# lcTempLogger.net
KiCad netlist of a schematic drawn in EAGLE
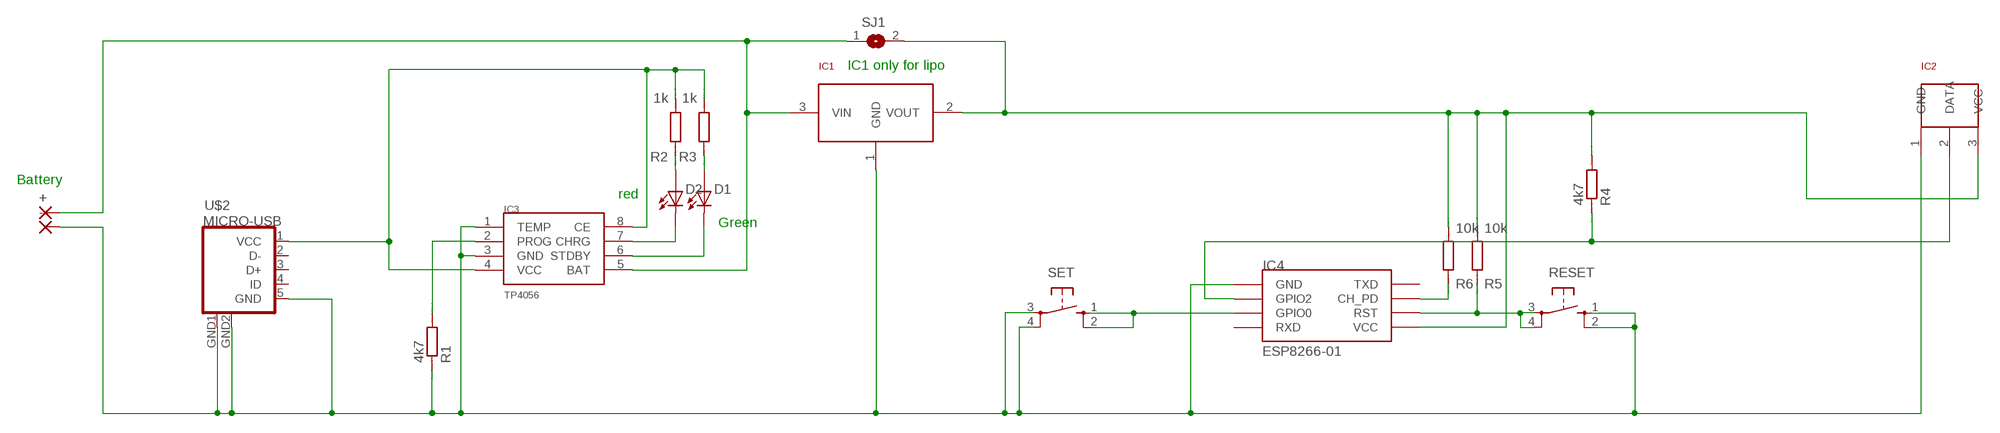
[diagram p0: schematic, sheet 1]

(export (version "E")
  (design (tool "Eeschema 10.0.6"))
  (components
    (comp (ref "+")
      (value "1,6/0,8")
      (footprint "eagle-import:1,6_0,8")
      (libsource (lib "eagle-import") (part "1,6/0,8"))
    )
    (comp (ref "-")
      (value "1,6/0,8")
      (footprint "eagle-import:1,6_0,8")
      (libsource (lib "eagle-import") (part "1,6/0,8"))
    )
    (comp (ref "D1")
      (value "LED-0805")
      (footprint "eagle-import:CHIPLED_0805")
      (libsource (lib "eagle-import") (part "LED-0805"))
    )
    (comp (ref "D2")
      (value "LED-0805")
      (footprint "eagle-import:CHIPLED_0805")
      (libsource (lib "eagle-import") (part "LED-0805"))
    )
    (comp (ref "IC1")
      (value "MCP1700")
      (footprint "eagle-import:SOT-23")
      (libsource (lib "eagle-import") (part "MCP1700SOT-32"))
    )
    (comp (ref "IC2")
      (value "DS18B20TO-92")
      (footprint "eagle-import:TO-92")
      (libsource (lib "eagle-import") (part "DS18B20TO-92"))
    )
    (comp (ref "IC3")
      (value "TP4056")
      (footprint "eagle-import:SOP-8")
      (libsource (lib "eagle-import") (part "TP4056"))
    )
    (comp (ref "IC4")
      (value "ESP8266-01")
      (footprint "eagle-import:ESP01")
      (libsource (lib "eagle-import") (part "ESP8266-01"))
    )
    (comp (ref "R1")
      (value "4k7")
      (footprint "eagle-import:R1206")
      (libsource (lib "eagle-import") (part "RR1206"))
    )
    (comp (ref "R2")
      (value "1k")
      (footprint "eagle-import:R0805")
      (libsource (lib "eagle-import") (part "R"))
    )
    (comp (ref "R3")
      (value "1k")
      (footprint "eagle-import:R0805")
      (libsource (lib "eagle-import") (part "R"))
    )
    (comp (ref "R4")
      (value "4k7")
      (footprint "eagle-import:R1206")
      (libsource (lib "eagle-import") (part "RR1206"))
    )
    (comp (ref "R5")
      (value "10k")
      (footprint "eagle-import:R1206")
      (libsource (lib "eagle-import") (part "RR1206"))
    )
    (comp (ref "R6")
      (value "10k")
      (footprint "eagle-import:R1206")
      (libsource (lib "eagle-import") (part "RR1206"))
    )
    (comp (ref "RESET")
      (value "10-XX")
      (footprint "eagle-import:B3F-10XX")
      (libsource (lib "eagle-import") (part "10-XX"))
    )
    (comp (ref "SET")
      (value "10-XX")
      (footprint "eagle-import:B3F-10XX")
      (libsource (lib "eagle-import") (part "10-XX"))
    )
    (comp (ref "SJ1") (value "SJ") (footprint "eagle-import:SJ") (libsource (lib "eagle-import") (part "SJ")))
    (comp (ref "U$2")
      (value "MICRO-USB")
      (footprint "eagle-import:MICRO-USB")
      (libsource (lib "eagle-import") (part "MICRO-USB"))
    )
  )
  (nets
    (net (code "1") (name "Net-(+-P)") (class "Default")
      (node (ref "+") (pin "1") (pinfunction "P_1") (pintype "passive"))
      (node (ref "IC1") (pin "3") (pinfunction "VIN_3") (pintype "bidirectional"))
      (node (ref "IC3") (pin "5") (pinfunction "BAT_5") (pintype "bidirectional"))
      (node (ref "SJ1") (pin "1") (pinfunction "1_1") (pintype "passive"))
    )
    (net (code "2") (name "Net-(--P)") (class "Default")
      (node (ref "-") (pin "1") (pinfunction "P_1") (pintype "passive"))
      (node (ref "IC1") (pin "1") (pinfunction "GND_1") (pintype "bidirectional"))
      (node (ref "IC2") (pin "1") (pinfunction "GND_1") (pintype "bidirectional"))
      (node (ref "IC3") (pin "1") (pinfunction "TEMP_1") (pintype "bidirectional"))
      (node (ref "IC3") (pin "3") (pinfunction "GND_3") (pintype "bidirectional"))
      (node (ref "IC4") (pin "GND") (pinfunction "GND_GND") (pintype "bidirectional"))
      (node (ref "R1") (pin "1") (pinfunction "1_1") (pintype "passive"))
      (node (ref "RESET") (pin "1") (pinfunction "1_1") (pintype "passive"))
      (node (ref "RESET") (pin "2") (pinfunction "2_2") (pintype "passive"))
      (node (ref "SET") (pin "3") (pinfunction "3_3") (pintype "passive"))
      (node (ref "SET") (pin "4") (pinfunction "4_4") (pintype "passive"))
      (node (ref "U$2") (pin "5") (pinfunction "GND_5") (pintype "power_in"))
      (node (ref "U$2") (pin "GND1") (pinfunction "GND_GND1") (pintype "power_in"))
      (node (ref "U$2") (pin "GND2") (pinfunction "GND_GND2") (pintype "power_in"))
    )
    (net (code "3") (name "Net-(D1-K)") (class "Default")
      (node (ref "D1") (pin "C") (pinfunction "K_C") (pintype "passive"))
      (node (ref "IC3") (pin "6") (pinfunction "STDBY_6") (pintype "bidirectional"))
    )
    (net (code "4") (name "Net-(D1-PadA)") (class "Default")
      (node (ref "D1") (pin "A") (pinfunction "A_A") (pintype "passive"))
      (node (ref "R3") (pin "1") (pinfunction "1_1") (pintype "passive"))
    )
    (net (code "5") (name "Net-(D2-K)") (class "Default")
      (node (ref "D2") (pin "C") (pinfunction "K_C") (pintype "passive"))
      (node (ref "IC3") (pin "7") (pinfunction "CHRG_7") (pintype "bidirectional"))
    )
    (net (code "6") (name "Net-(D2-PadA)") (class "Default")
      (node (ref "D2") (pin "A") (pinfunction "A_A") (pintype "passive"))
      (node (ref "R2") (pin "1") (pinfunction "1_1") (pintype "passive"))
    )
    (net (code "7") (name "Net-(IC1-VOUT)") (class "Default")
      (node (ref "IC1") (pin "2") (pinfunction "VOUT_2") (pintype "bidirectional"))
      (node (ref "IC2") (pin "3") (pinfunction "VCC_3") (pintype "bidirectional"))
      (node (ref "IC4") (pin "VCC") (pinfunction "VCC_VCC") (pintype "bidirectional"))
      (node (ref "R4") (pin "2") (pinfunction "2_2") (pintype "passive"))
      (node (ref "R5") (pin "2") (pinfunction "2_2") (pintype "passive"))
      (node (ref "R6") (pin "2") (pinfunction "2_2") (pintype "passive"))
      (node (ref "SJ1") (pin "2") (pinfunction "2_2") (pintype "passive"))
    )
    (net (code "8") (name "Net-(IC2-DATA)") (class "Default")
      (node (ref "IC2") (pin "2") (pinfunction "DATA_2") (pintype "bidirectional"))
      (node (ref "IC4") (pin "GPIO2") (pinfunction "GPIO2_GPIO2") (pintype "bidirectional"))
      (node (ref "R4") (pin "1") (pinfunction "1_1") (pintype "passive"))
    )
    (net (code "9") (name "Net-(IC3-CE)") (class "Default")
      (node (ref "IC3") (pin "4") (pinfunction "VCC_4") (pintype "bidirectional"))
      (node (ref "IC3") (pin "8") (pinfunction "CE_8") (pintype "bidirectional"))
      (node (ref "R2") (pin "2") (pinfunction "2_2") (pintype "passive"))
      (node (ref "R3") (pin "2") (pinfunction "2_2") (pintype "passive"))
      (node (ref "U$2") (pin "1") (pinfunction "VCC_1") (pintype "power_in"))
    )
    (net (code "10") (name "Net-(IC3-PROG)") (class "Default")
      (node (ref "IC3") (pin "2") (pinfunction "PROG_2") (pintype "bidirectional"))
      (node (ref "R1") (pin "2") (pinfunction "2_2") (pintype "passive"))
    )
    (net (code "11") (name "Net-(IC4-PadCH_PD)") (class "Default")
      (node (ref "IC4") (pin "CH_PD") (pinfunction "CH_PD_CH_PD") (pintype "bidirectional"))
      (node (ref "R6") (pin "1") (pinfunction "1_1") (pintype "passive"))
    )
    (net (code "12") (name "Net-(IC4-PadGPIO0)") (class "Default")
      (node (ref "IC4") (pin "GPIO0") (pinfunction "GPIO0_GPIO0") (pintype "bidirectional"))
      (node (ref "SET") (pin "1") (pinfunction "1_1") (pintype "passive"))
      (node (ref "SET") (pin "2") (pinfunction "2_2") (pintype "passive"))
    )
    (net (code "13") (name "Net-(IC4-PadRST)") (class "Default")
      (node (ref "IC4") (pin "RST") (pinfunction "RST_RST") (pintype "bidirectional"))
      (node (ref "R5") (pin "1") (pinfunction "1_1") (pintype "passive"))
      (node (ref "RESET") (pin "3") (pinfunction "3_3") (pintype "passive"))
      (node (ref "RESET") (pin "4") (pinfunction "4_4") (pintype "passive"))
    )
    (net (code "14") (name "unconnected-(IC4-RXD-PadRX)") (class "Default")
      (node (ref "IC4") (pin "RX") (pinfunction "RXD_RX") (pintype "bidirectional"))
    )
    (net (code "15") (name "unconnected-(IC4-TXD-PadTX)") (class "Default")
      (node (ref "IC4") (pin "TX") (pinfunction "TXD_TX") (pintype "bidirectional"))
    )
    (net (code "16") (name "unconnected-(U$2-D+-Pad3)") (class "Default")
      (node (ref "U$2") (pin "3") (pinfunction "D+_3") (pintype "bidirectional"))
    )
    (net (code "17") (name "unconnected-(U$2-D--Pad2)") (class "Default")
      (node (ref "U$2") (pin "2") (pinfunction "D-_2") (pintype "bidirectional"))
    )
    (net (code "18") (name "unconnected-(U$2-ID-Pad4)") (class "Default")
      (node (ref "U$2") (pin "4") (pinfunction "ID_4") (pintype "bidirectional"))
    )
  )
)
